# blynk_light_switch_v1.net
KiCad netlist of a schematic drawn in EAGLE
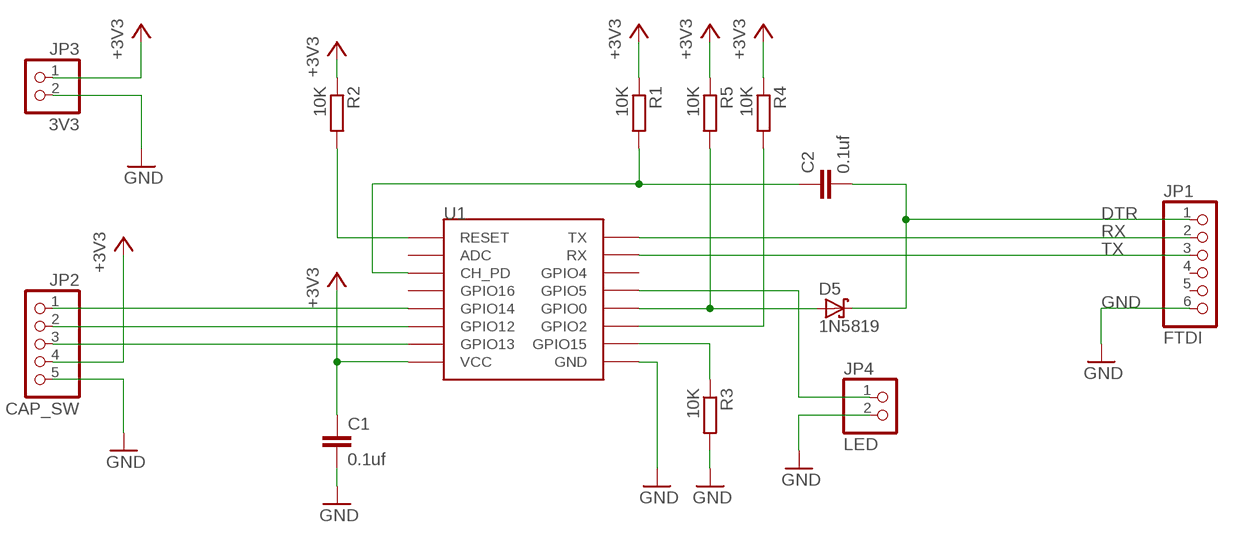
[diagram p0: schematic, sheet 1]

(export (version "E")
  (design (tool "Eeschema 10.0.6"))
  (components
    (comp (ref "C1")
      (value "0.1uf")
      (footprint "eagle-import:C0805")
      (libsource (lib "eagle-import") (part "C-EUC0805"))
    )
    (comp (ref "C2")
      (value "0.1uf")
      (footprint "eagle-import:C0805")
      (libsource (lib "eagle-import") (part "C-EUC0805"))
    )
    (comp (ref "D5")
      (value "1N5819")
      (footprint "eagle-import:CB429-17")
      (libsource (lib "eagle-import") (part "SCHOTTKY-DIODECB429-17"))
    )
    (comp (ref "JP1")
      (value "FTDI")
      (footprint "eagle-import:1X06")
      (libsource (lib "eagle-import") (part "PINHD-1X6"))
    )
    (comp (ref "JP2")
      (value "CAP_SW")
      (footprint "eagle-import:1X05")
      (libsource (lib "eagle-import") (part "PINHD-1X5"))
    )
    (comp (ref "JP3")
      (value "3V3")
      (footprint "eagle-import:1X02")
      (libsource (lib "eagle-import") (part "PINHD-1X2"))
    )
    (comp (ref "JP4")
      (value "LED")
      (footprint "eagle-import:1X02")
      (libsource (lib "eagle-import") (part "PINHD-1X2"))
    )
    (comp (ref "R1")
      (value "10K")
      (footprint "eagle-import:R0805")
      (fields (field (name "MF") "ARCOL/OHMITE") (field (name "MPN") "MRA0207 100K B 15PPM TA"))
      (libsource (lib "eagle-import") (part "R-EU_R0805"))
    )
    (comp (ref "R2")
      (value "10K")
      (footprint "eagle-import:R0805")
      (fields (field (name "MF") "ARCOL/OHMITE") (field (name "MPN") "MRA0207 100K B 15PPM TA"))
      (libsource (lib "eagle-import") (part "R-EU_R0805"))
    )
    (comp (ref "R3")
      (value "10K")
      (footprint "eagle-import:R0805")
      (fields (field (name "MF") "ARCOL/OHMITE") (field (name "MPN") "MRA0207 100K B 15PPM TA"))
      (libsource (lib "eagle-import") (part "R-EU_R0805"))
    )
    (comp (ref "R4")
      (value "10K")
      (footprint "eagle-import:R0805")
      (fields (field (name "MF") "ARCOL/OHMITE") (field (name "MPN") "MRA0207 100K B 15PPM TA"))
      (libsource (lib "eagle-import") (part "R-EU_R0805"))
    )
    (comp (ref "R5")
      (value "10K")
      (footprint "eagle-import:R0805")
      (fields (field (name "MF") "ARCOL/OHMITE") (field (name "MPN") "MRA0207 100K B 15PPM TA"))
      (libsource (lib "eagle-import") (part "R-EU_R0805"))
    )
    (comp (ref "U1")
      (value "ESP12SMD")
      (footprint "eagle-import:ESP12-SMD")
      (libsource (lib "eagle-import") (part "ESP12SMD"))
    )
  )
  (nets
    (net (code "1") (name "+3V3") (class "Default")
      (node (ref "C1") (pin "1") (pinfunction "1_1") (pintype "passive"))
      (node (ref "JP2") (pin "4") (pinfunction "4_4") (pintype "passive"))
      (node (ref "JP3") (pin "1") (pinfunction "1_1") (pintype "passive"))
      (node (ref "R1") (pin "1") (pinfunction "1_1") (pintype "passive"))
      (node (ref "R2") (pin "1") (pinfunction "1_1") (pintype "passive"))
      (node (ref "R4") (pin "1") (pinfunction "1_1") (pintype "passive"))
      (node (ref "R5") (pin "1") (pinfunction "1_1") (pintype "passive"))
      (node (ref "U1") (pin "VCC") (pinfunction "VCC_VCC") (pintype "bidirectional"))
    )
    (net (code "2") (name "/DTR") (class "Default")
      (node (ref "C2") (pin "2") (pinfunction "2_2") (pintype "passive"))
      (node (ref "D5") (pin "C") (pinfunction "C_C") (pintype "passive"))
      (node (ref "JP1") (pin "1") (pinfunction "1_1") (pintype "passive"))
    )
    (net (code "3") (name "/RX") (class "Default")
      (node (ref "JP1") (pin "2") (pinfunction "2_2") (pintype "passive"))
      (node (ref "U1") (pin "TXD0") (pinfunction "TX_TXD0") (pintype "bidirectional"))
    )
    (net (code "4") (name "/TX") (class "Default")
      (node (ref "JP1") (pin "3") (pinfunction "3_3") (pintype "passive"))
      (node (ref "U1") (pin "RXD0") (pinfunction "RX_RXD0") (pintype "bidirectional"))
    )
    (net (code "5") (name "GND") (class "Default")
      (node (ref "C1") (pin "2") (pinfunction "2_2") (pintype "passive"))
      (node (ref "JP1") (pin "6") (pinfunction "6_6") (pintype "passive"))
      (node (ref "JP2") (pin "5") (pinfunction "5_5") (pintype "passive"))
      (node (ref "JP3") (pin "2") (pinfunction "2_2") (pintype "passive"))
      (node (ref "JP4") (pin "2") (pinfunction "2_2") (pintype "passive"))
      (node (ref "R3") (pin "2") (pinfunction "2_2") (pintype "passive"))
      (node (ref "U1") (pin "GND") (pinfunction "GND_GND") (pintype "bidirectional"))
    )
    (net (code "6") (name "Net-(C2-Pad1)") (class "Default")
      (node (ref "C2") (pin "1") (pinfunction "1_1") (pintype "passive"))
      (node (ref "R1") (pin "2") (pinfunction "2_2") (pintype "passive"))
      (node (ref "U1") (pin "CH_PD") (pinfunction "CH_PD_CH_PD") (pintype "bidirectional"))
    )
    (net (code "7") (name "Net-(D5-PadA)") (class "Default")
      (node (ref "D5") (pin "A") (pinfunction "A_A") (pintype "passive"))
      (node (ref "R5") (pin "2") (pinfunction "2_2") (pintype "passive"))
      (node (ref "U1") (pin "GPIO0") (pinfunction "GPIO0_GPIO0") (pintype "bidirectional"))
    )
    (net (code "8") (name "Net-(JP2-Pad1)") (class "Default")
      (node (ref "JP2") (pin "1") (pinfunction "1_1") (pintype "passive"))
      (node (ref "U1") (pin "GPIO14") (pinfunction "GPIO14_GPIO14") (pintype "bidirectional"))
    )
    (net (code "9") (name "Net-(JP2-Pad2)") (class "Default")
      (node (ref "JP2") (pin "2") (pinfunction "2_2") (pintype "passive"))
      (node (ref "U1") (pin "GPIO12") (pinfunction "GPIO12_GPIO12") (pintype "bidirectional"))
    )
    (net (code "10") (name "Net-(JP2-Pad3)") (class "Default")
      (node (ref "JP2") (pin "3") (pinfunction "3_3") (pintype "passive"))
      (node (ref "U1") (pin "GPIO13") (pinfunction "GPIO13_GPIO13") (pintype "bidirectional"))
    )
    (net (code "11") (name "Net-(JP4-Pad1)") (class "Default")
      (node (ref "JP4") (pin "1") (pinfunction "1_1") (pintype "passive"))
      (node (ref "U1") (pin "GPIO5") (pinfunction "GPIO5_GPIO5") (pintype "bidirectional"))
    )
    (net (code "12") (name "Net-(R2-Pad2)") (class "Default")
      (node (ref "R2") (pin "2") (pinfunction "2_2") (pintype "passive"))
      (node (ref "U1") (pin "RESET") (pinfunction "RESET_RESET") (pintype "bidirectional"))
    )
    (net (code "13") (name "Net-(R3-Pad1)") (class "Default")
      (node (ref "R3") (pin "1") (pinfunction "1_1") (pintype "passive"))
      (node (ref "U1") (pin "GPIO15") (pinfunction "GPIO15_GPIO15") (pintype "bidirectional"))
    )
    (net (code "14") (name "Net-(R4-Pad2)") (class "Default")
      (node (ref "R4") (pin "2") (pinfunction "2_2") (pintype "passive"))
      (node (ref "U1") (pin "GPIO2") (pinfunction "GPIO2_GPIO2") (pintype "bidirectional"))
    )
    (net (code "15") (name "unconnected-(JP1-Pad4)") (class "Default")
      (node (ref "JP1") (pin "4") (pinfunction "4_4") (pintype "passive"))
    )
    (net (code "16") (name "unconnected-(JP1-Pad5)") (class "Default")
      (node (ref "JP1") (pin "5") (pinfunction "5_5") (pintype "passive"))
    )
    (net (code "17") (name "unconnected-(U1-PadADC)") (class "Default")
      (node (ref "U1") (pin "ADC") (pinfunction "ADC_ADC") (pintype "bidirectional"))
    )
    (net (code "18") (name "unconnected-(U1-PadGPIO4)") (class "Default")
      (node (ref "U1") (pin "GPIO4") (pinfunction "GPIO4_GPIO4") (pintype "bidirectional"))
    )
    (net (code "19") (name "unconnected-(U1-PadGPIO16)") (class "Default")
      (node (ref "U1") (pin "GPIO16") (pinfunction "GPIO16_GPIO16") (pintype "bidirectional"))
    )
  )
)
